# s3_dev.net
KiCad netlist of a schematic drawn in EasyEDA
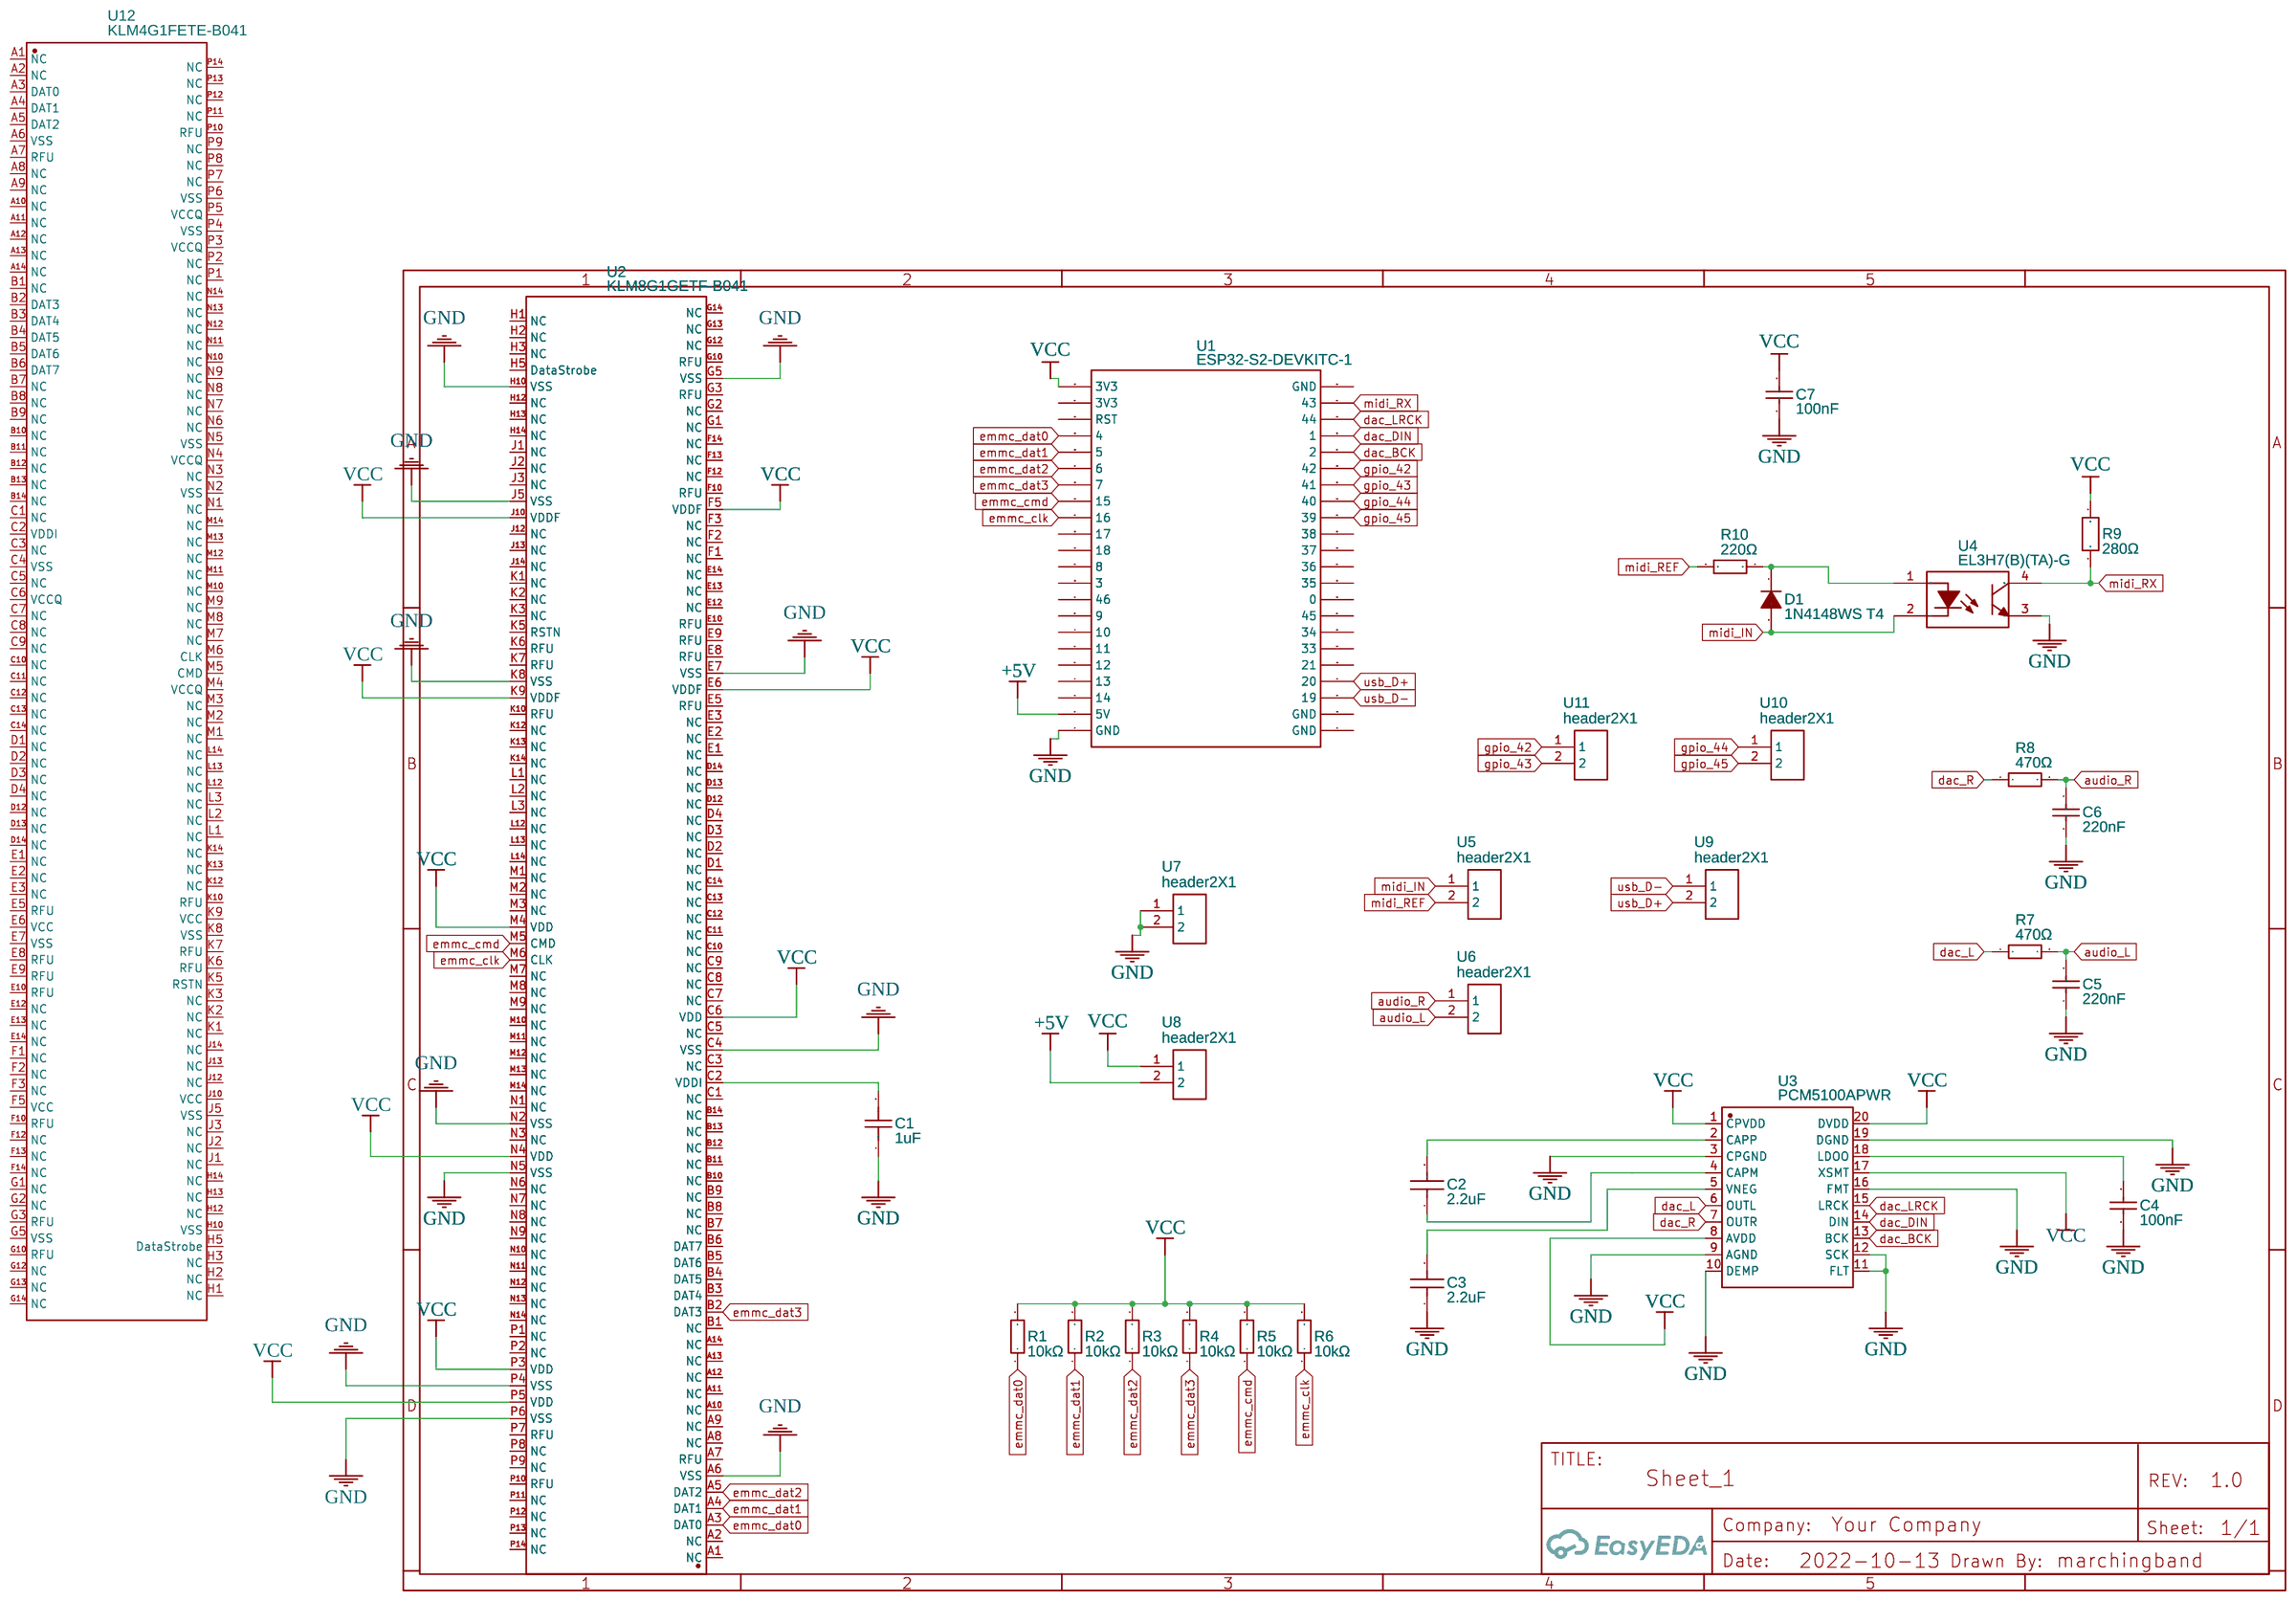
[diagram p0: schematic sheet]

(export (version "E")
  (design (tool "Eeschema 10.0.6"))
  (components
    (comp (ref "C1")
      (value "1uF")
      (fields
        (field (name "BOM_Manufacturer Part") "CL05A105KA5NQNC")
        (field (name "BOM_Supplier Part") "C52923")
      )
      (libsource (lib "") (part "CL05A105KA5NQNC"))
    )
    (comp (ref "C2")
      (value "2.2uF")
      (fields
        (field (name "BOM_Manufacturer Part") "CL05A225MQ5NSNC")
        (field (name "BOM_Supplier Part") "C12530")
      )
      (libsource (lib "") (part "CL05A225MQ5NSNC"))
    )
    (comp (ref "C3")
      (value "2.2uF")
      (fields
        (field (name "BOM_Manufacturer Part") "CL05A225MQ5NSNC")
        (field (name "BOM_Supplier Part") "C12530")
      )
      (libsource (lib "") (part "CL05A225MQ5NSNC"))
    )
    (comp (ref "C4")
      (value "100nF")
      (fields
        (field (name "BOM_Manufacturer Part") "CL05B104KO5NNNC")
        (field (name "BOM_Supplier Part") "C1525")
      )
      (libsource (lib "") (part "CL05B104KO5NNNC"))
    )
    (comp (ref "C5")
      (value "220nF")
      (fields
        (field (name "BOM_Manufacturer Part") "CL05B224KO5NNNC")
        (field (name "BOM_Supplier Part") "C16772")
      )
      (libsource (lib "") (part "CL05B224KO5NNNC"))
    )
    (comp (ref "C6")
      (value "220nF")
      (fields
        (field (name "BOM_Manufacturer Part") "CL05B224KO5NNNC")
        (field (name "BOM_Supplier Part") "C16772")
      )
      (libsource (lib "") (part "CL05B224KO5NNNC"))
    )
    (comp (ref "C7")
      (value "100nF")
      (fields
        (field (name "BOM_Manufacturer Part") "CL05B104KO5NNNC")
        (field (name "BOM_Supplier Part") "C1525")
      )
      (libsource (lib "") (part "CL05B104KO5NNNC"))
    )
    (comp (ref "D1")
      (value "1N4148WS T4")
      (fields (field (name "BOM_Supplier Part") "C2128"))
      (libsource (lib "") (part "1N4148WS T4"))
    )
    (comp (ref "R1")
      (value "10kΩ")
      (fields
        (field (name "BOM_Manufacturer Part") "0402WGF1002TCE")
        (field (name "BOM_Supplier Part") "C25744")
      )
      (libsource (lib "") (part "0402WGF1002TCE"))
    )
    (comp (ref "R2")
      (value "10kΩ")
      (fields
        (field (name "BOM_Manufacturer Part") "0402WGF1002TCE")
        (field (name "BOM_Supplier Part") "C25744")
      )
      (libsource (lib "") (part "0402WGF1002TCE"))
    )
    (comp (ref "R3")
      (value "10kΩ")
      (fields
        (field (name "BOM_Manufacturer Part") "0402WGF1002TCE")
        (field (name "BOM_Supplier Part") "C25744")
      )
      (libsource (lib "") (part "0402WGF1002TCE"))
    )
    (comp (ref "R4")
      (value "10kΩ")
      (fields
        (field (name "BOM_Manufacturer Part") "0402WGF1002TCE")
        (field (name "BOM_Supplier Part") "C25744")
      )
      (libsource (lib "") (part "0402WGF1002TCE"))
    )
    (comp (ref "R5")
      (value "10kΩ")
      (fields
        (field (name "BOM_Manufacturer Part") "0402WGF1002TCE")
        (field (name "BOM_Supplier Part") "C25744")
      )
      (libsource (lib "") (part "0402WGF1002TCE"))
    )
    (comp (ref "R6")
      (value "10kΩ")
      (fields
        (field (name "BOM_Manufacturer Part") "0402WGF1002TCE")
        (field (name "BOM_Supplier Part") "C25744")
      )
      (libsource (lib "") (part "0402WGF1002TCE"))
    )
    (comp (ref "R7")
      (value "470Ω")
      (fields
        (field (name "BOM_Manufacturer Part") "0402WGF4700TCE")
        (field (name "BOM_Supplier Part") "C25117")
      )
      (libsource (lib "") (part "0402WGF4700TCE"))
    )
    (comp (ref "R8")
      (value "470Ω")
      (fields
        (field (name "BOM_Manufacturer Part") "0402WGF4700TCE")
        (field (name "BOM_Supplier Part") "C25117")
      )
      (libsource (lib "") (part "0402WGF4700TCE"))
    )
    (comp (ref "R9")
      (value "280Ω")
      (fields
        (field (name "BOM_Manufacturer Part") "0402WGF2800TCE")
        (field (name "BOM_Supplier Part") "C423200")
      )
      (libsource (lib "") (part "0402WGF2800TCE"))
    )
    (comp (ref "R10")
      (value "220Ω")
      (fields
        (field (name "BOM_Manufacturer Part") "0402WGF2200TCE")
        (field (name "BOM_Supplier Part") "C25091")
      )
      (libsource (lib "") (part "0402WGF2200TCE"))
    )
    (comp (ref "U1")
      (value "ESP32-S2-DEVKITC-1")
      (fields (field (name "BOM_Supplier Part") "ESP32-S3-DevKitC-1"))
      (libsource (lib "") (part "ESP32-S2-DEVKITC-1"))
    )
    (comp (ref "U2")
      (value "KLM8G1GETF-B041")
      (fields (field (name "BOM_Supplier Part") "C499918"))
      (libsource (lib "") (part "KLM8G1GETF-B041"))
    )
    (comp (ref "U3")
      (value "PCM5100APWR")
      (fields (field (name "BOM_Supplier Part") "C131154"))
      (libsource (lib "") (part "PCM5100APWR"))
    )
    (comp (ref "U4")
      (value "EL3H7(B)(TA)-G")
      (fields (field (name "BOM_Supplier Part") "C32565"))
      (libsource (lib "") (part "EL3H7(B)(TA)-G"))
    )
    (comp (ref "U5") (value "header2X1") (libsource (lib "") (part "header2X1")))
    (comp (ref "U6") (value "header2X1") (libsource (lib "") (part "header2X1")))
    (comp (ref "U7") (value "header2X1") (libsource (lib "") (part "header2X1")))
    (comp (ref "U8") (value "header2X1") (libsource (lib "") (part "header2X1")))
    (comp (ref "U9") (value "header2X1") (libsource (lib "") (part "header2X1")))
    (comp (ref "U10") (value "header2X1") (libsource (lib "") (part "header2X1")))
    (comp (ref "U11") (value "header2X1") (libsource (lib "") (part "header2X1")))
    (comp (ref "U12")
      (value "KLM4G1FETE-B041")
      (fields (field (name "BOM_Supplier Part") "C500273"))
      (libsource (lib "") (part "KLM4G1FETE-B041"))
    )
  )
  (nets
    (net (code "1") (name "+5V") (class "Default")
      (node (ref "U1") (pin "2") (pinfunction "5V_2") (pintype "passive"))
      (node (ref "U8") (pin "2") (pinfunction "2_2") (pintype "unspecified"))
    )
    (net (code "2") (name "GND") (class "Default")
      (node (ref "C1") (pin "1") (pinfunction "1_1") (pintype "unspecified"))
      (node (ref "C3") (pin "1") (pinfunction "1_1") (pintype "unspecified"))
      (node (ref "C4") (pin "1") (pinfunction "1_1") (pintype "input"))
      (node (ref "C5") (pin "1") (pinfunction "1_1") (pintype "input"))
      (node (ref "C6") (pin "1") (pinfunction "1_1") (pintype "input"))
      (node (ref "C7") (pin "1") (pinfunction "1_1") (pintype "input"))
      (node (ref "U1") (pin "1") (pinfunction "GND_1") (pintype "unspecified"))
      (node (ref "U2") (pin "A6") (pinfunction "VSS_A6") (pintype "unspecified"))
      (node (ref "U2") (pin "C4") (pinfunction "VSS_C4") (pintype "unspecified"))
      (node (ref "U2") (pin "E7") (pinfunction "VSS_E7") (pintype "unspecified"))
      (node (ref "U2") (pin "G5") (pinfunction "VSS_G5") (pintype "unspecified"))
      (node (ref "U2") (pin "H10") (pinfunction "VSS_H10") (pintype "unspecified"))
      (node (ref "U2") (pin "J5") (pinfunction "VSS_J5") (pintype "unspecified"))
      (node (ref "U2") (pin "K8") (pinfunction "VSS_K8") (pintype "unspecified"))
      (node (ref "U2") (pin "N2") (pinfunction "VSS_N2") (pintype "unspecified"))
      (node (ref "U2") (pin "N5") (pinfunction "VSS_N5") (pintype "unspecified"))
      (node (ref "U2") (pin "P4") (pinfunction "VSS_P4") (pintype "unspecified"))
      (node (ref "U2") (pin "P6") (pinfunction "VSS_P6") (pintype "unspecified"))
      (node (ref "U3") (pin "10") (pinfunction "DEMP_10") (pintype "unspecified"))
      (node (ref "U3") (pin "11") (pinfunction "FLT_11") (pintype "unspecified"))
      (node (ref "U3") (pin "12") (pinfunction "SCK_12") (pintype "unspecified"))
      (node (ref "U3") (pin "16") (pinfunction "FMT_16") (pintype "unspecified"))
      (node (ref "U3") (pin "19") (pinfunction "DGND_19") (pintype "unspecified"))
      (node (ref "U3") (pin "3") (pinfunction "CPGND_3") (pintype "unspecified"))
      (node (ref "U3") (pin "9") (pinfunction "AGND_9") (pintype "unspecified"))
      (node (ref "U4") (pin "3") (pinfunction "EM_3") (pintype "unspecified"))
      (node (ref "U7") (pin "1") (pinfunction "1_1") (pintype "unspecified"))
      (node (ref "U7") (pin "2") (pinfunction "2_2") (pintype "unspecified"))
    )
    (net (code "3") (name "Net-(D1-K)") (class "Default")
      (node (ref "D1") (pin "1") (pinfunction "K_1") (pintype "unspecified"))
      (node (ref "R10") (pin "2") (pinfunction "2_2") (pintype "input"))
      (node (ref "U4") (pin "1") (pinfunction "AN_1") (pintype "unspecified"))
    )
    (net (code "4") (name "Net-(U2-VDDI)") (class "Default")
      (node (ref "C1") (pin "2") (pinfunction "2_2") (pintype "unspecified"))
      (node (ref "U2") (pin "C2") (pinfunction "VDDI_C2") (pintype "unspecified"))
    )
    (net (code "5") (name "Net-(U3-CAPM)") (class "Default")
      (node (ref "C2") (pin "1") (pinfunction "1_1") (pintype "unspecified"))
      (node (ref "U3") (pin "4") (pinfunction "CAPM_4") (pintype "unspecified"))
    )
    (net (code "6") (name "Net-(U3-CAPP)") (class "Default")
      (node (ref "C2") (pin "2") (pinfunction "2_2") (pintype "unspecified"))
      (node (ref "U3") (pin "2") (pinfunction "CAPP_2") (pintype "unspecified"))
    )
    (net (code "7") (name "Net-(U3-LDOO)") (class "Default")
      (node (ref "C4") (pin "2") (pinfunction "2_2") (pintype "input"))
      (node (ref "U3") (pin "18") (pinfunction "LDOO_18") (pintype "unspecified"))
    )
    (net (code "8") (name "Net-(U3-VNEG)") (class "Default")
      (node (ref "C3") (pin "2") (pinfunction "2_2") (pintype "unspecified"))
      (node (ref "U3") (pin "5") (pinfunction "VNEG_5") (pintype "unspecified"))
    )
    (net (code "9") (name "VCC") (class "Default")
      (node (ref "C7") (pin "2") (pinfunction "2_2") (pintype "input"))
      (node (ref "R1") (pin "2") (pinfunction "2_2") (pintype "input"))
      (node (ref "R2") (pin "2") (pinfunction "2_2") (pintype "input"))
      (node (ref "R3") (pin "2") (pinfunction "2_2") (pintype "input"))
      (node (ref "R4") (pin "2") (pinfunction "2_2") (pintype "input"))
      (node (ref "R5") (pin "2") (pinfunction "2_2") (pintype "input"))
      (node (ref "R6") (pin "2") (pinfunction "2_2") (pintype "input"))
      (node (ref "R9") (pin "2") (pinfunction "2_2") (pintype "unspecified"))
      (node (ref "U1") (pin "22") (pinfunction "3V3_22") (pintype "passive"))
      (node (ref "U2") (pin "C6") (pinfunction "VDD_C6") (pintype "unspecified"))
      (node (ref "U2") (pin "E6") (pinfunction "VDDF_E6") (pintype "unspecified"))
      (node (ref "U2") (pin "F5") (pinfunction "VDDF_F5") (pintype "unspecified"))
      (node (ref "U2") (pin "J10") (pinfunction "VDDF_J10") (pintype "unspecified"))
      (node (ref "U2") (pin "K9") (pinfunction "VDDF_K9") (pintype "unspecified"))
      (node (ref "U2") (pin "M4") (pinfunction "VDD_M4") (pintype "unspecified"))
      (node (ref "U2") (pin "N4") (pinfunction "VDD_N4") (pintype "unspecified"))
      (node (ref "U2") (pin "P3") (pinfunction "VDD_P3") (pintype "unspecified"))
      (node (ref "U2") (pin "P5") (pinfunction "VDD_P5") (pintype "unspecified"))
      (node (ref "U3") (pin "1") (pinfunction "CPVDD_1") (pintype "unspecified"))
      (node (ref "U3") (pin "17") (pinfunction "XSMT_17") (pintype "unspecified"))
      (node (ref "U3") (pin "20") (pinfunction "DVDD_20") (pintype "unspecified"))
      (node (ref "U3") (pin "8") (pinfunction "AVDD_8") (pintype "unspecified"))
      (node (ref "U8") (pin "1") (pinfunction "1_1") (pintype "unspecified"))
    )
    (net (code "10") (name "audio_L") (class "Default")
      (node (ref "C5") (pin "2") (pinfunction "2_2") (pintype "input"))
      (node (ref "R7") (pin "2") (pinfunction "2_2") (pintype "input"))
      (node (ref "U6") (pin "2") (pinfunction "2_2") (pintype "unspecified"))
    )
    (net (code "11") (name "audio_R") (class "Default")
      (node (ref "C6") (pin "2") (pinfunction "2_2") (pintype "input"))
      (node (ref "R8") (pin "2") (pinfunction "2_2") (pintype "input"))
      (node (ref "U6") (pin "1") (pinfunction "1_1") (pintype "unspecified"))
    )
    (net (code "12") (name "dac_BCK") (class "Default")
      (node (ref "U1") (pin "27") (pinfunction "2_27") (pintype "bidirectional"))
      (node (ref "U3") (pin "13") (pinfunction "BCK_13") (pintype "unspecified"))
    )
    (net (code "13") (name "dac_DIN") (class "Default")
      (node (ref "U1") (pin "26") (pinfunction "1_26") (pintype "bidirectional"))
      (node (ref "U3") (pin "14") (pinfunction "DIN_14") (pintype "unspecified"))
    )
    (net (code "14") (name "dac_L") (class "Default")
      (node (ref "R7") (pin "1") (pinfunction "1_1") (pintype "input"))
      (node (ref "U3") (pin "6") (pinfunction "OUTL_6") (pintype "unspecified"))
    )
    (net (code "15") (name "dac_LRCK") (class "Default")
      (node (ref "U1") (pin "25") (pinfunction "44_25") (pintype "bidirectional"))
      (node (ref "U3") (pin "15") (pinfunction "LRCK_15") (pintype "unspecified"))
    )
    (net (code "16") (name "dac_R") (class "Default")
      (node (ref "R8") (pin "1") (pinfunction "1_1") (pintype "input"))
      (node (ref "U3") (pin "7") (pinfunction "OUTR_7") (pintype "unspecified"))
    )
    (net (code "17") (name "emmc_clk") (class "Default")
      (node (ref "R6") (pin "1") (pinfunction "1_1") (pintype "input"))
      (node (ref "U1") (pin "14") (pinfunction "16_14") (pintype "bidirectional"))
      (node (ref "U2") (pin "M6") (pinfunction "CLK_M6") (pintype "unspecified"))
    )
    (net (code "18") (name "emmc_cmd") (class "Default")
      (node (ref "R5") (pin "1") (pinfunction "1_1") (pintype "input"))
      (node (ref "U1") (pin "15") (pinfunction "15_15") (pintype "bidirectional"))
      (node (ref "U2") (pin "M5") (pinfunction "CMD_M5") (pintype "unspecified"))
    )
    (net (code "19") (name "emmc_dat0") (class "Default")
      (node (ref "R1") (pin "1") (pinfunction "1_1") (pintype "input"))
      (node (ref "U1") (pin "19") (pinfunction "4_19") (pintype "bidirectional"))
      (node (ref "U2") (pin "A3") (pinfunction "DAT0_A3") (pintype "unspecified"))
    )
    (net (code "20") (name "emmc_dat1") (class "Default")
      (node (ref "R2") (pin "1") (pinfunction "1_1") (pintype "input"))
      (node (ref "U1") (pin "18") (pinfunction "5_18") (pintype "bidirectional"))
      (node (ref "U2") (pin "A4") (pinfunction "DAT1_A4") (pintype "unspecified"))
    )
    (net (code "21") (name "emmc_dat2") (class "Default")
      (node (ref "R3") (pin "1") (pinfunction "1_1") (pintype "input"))
      (node (ref "U1") (pin "17") (pinfunction "6_17") (pintype "bidirectional"))
      (node (ref "U2") (pin "A5") (pinfunction "DAT2_A5") (pintype "unspecified"))
    )
    (net (code "22") (name "emmc_dat3") (class "Default")
      (node (ref "R4") (pin "1") (pinfunction "1_1") (pintype "input"))
      (node (ref "U1") (pin "16") (pinfunction "7_16") (pintype "bidirectional"))
      (node (ref "U2") (pin "B2") (pinfunction "DAT3_B2") (pintype "unspecified"))
    )
    (net (code "23") (name "gpio_42") (class "Default")
      (node (ref "U1") (pin "28") (pinfunction "42_28") (pintype "bidirectional"))
      (node (ref "U11") (pin "1") (pinfunction "1_1") (pintype "unspecified"))
    )
    (net (code "24") (name "gpio_43") (class "Default")
      (node (ref "U1") (pin "29") (pinfunction "41_29") (pintype "bidirectional"))
      (node (ref "U11") (pin "2") (pinfunction "2_2") (pintype "unspecified"))
    )
    (net (code "25") (name "gpio_44") (class "Default")
      (node (ref "U1") (pin "30") (pinfunction "40_30") (pintype "bidirectional"))
      (node (ref "U10") (pin "1") (pinfunction "1_1") (pintype "unspecified"))
    )
    (net (code "26") (name "gpio_45") (class "Default")
      (node (ref "U1") (pin "31") (pinfunction "39_31") (pintype "bidirectional"))
      (node (ref "U10") (pin "2") (pinfunction "2_2") (pintype "unspecified"))
    )
    (net (code "27") (name "midi_IN") (class "Default")
      (node (ref "D1") (pin "2") (pinfunction "A_2") (pintype "unspecified"))
      (node (ref "U4") (pin "2") (pinfunction "CAT_2") (pintype "unspecified"))
      (node (ref "U5") (pin "1") (pinfunction "1_1") (pintype "unspecified"))
    )
    (net (code "28") (name "midi_REF") (class "Default")
      (node (ref "R10") (pin "1") (pinfunction "1_1") (pintype "input"))
      (node (ref "U5") (pin "2") (pinfunction "2_2") (pintype "unspecified"))
    )
    (net (code "29") (name "midi_RX") (class "Default")
      (node (ref "R9") (pin "1") (pinfunction "1_1") (pintype "unspecified"))
      (node (ref "U1") (pin "24") (pinfunction "43_24") (pintype "bidirectional"))
      (node (ref "U4") (pin "4") (pinfunction "COL_4") (pintype "unspecified"))
    )
    (net (code "30") (name "unconnected-(U1-0-Pad36)") (class "Default")
      (node (ref "U1") (pin "36") (pinfunction "0_36") (pintype "bidirectional"))
    )
    (net (code "31") (name "unconnected-(U1-3-Pad10)") (class "Default")
      (node (ref "U1") (pin "10") (pinfunction "3_10") (pintype "bidirectional"))
    )
    (net (code "32") (name "unconnected-(U1-3V3-Pad21)") (class "Default")
      (node (ref "U1") (pin "21") (pinfunction "3V3_21") (pintype "passive"))
    )
    (net (code "33") (name "unconnected-(U1-8-Pad11)") (class "Default")
      (node (ref "U1") (pin "11") (pinfunction "8_11") (pintype "bidirectional"))
    )
    (net (code "34") (name "unconnected-(U1-9-Pad8)") (class "Default")
      (node (ref "U1") (pin "8") (pinfunction "9_8") (pintype "bidirectional"))
    )
    (net (code "35") (name "unconnected-(U1-10-Pad7)") (class "Default")
      (node (ref "U1") (pin "7") (pinfunction "10_7") (pintype "bidirectional"))
    )
    (net (code "36") (name "unconnected-(U1-11-Pad6)") (class "Default")
      (node (ref "U1") (pin "6") (pinfunction "11_6") (pintype "bidirectional"))
    )
    (net (code "37") (name "unconnected-(U1-12-Pad5)") (class "Default")
      (node (ref "U1") (pin "5") (pinfunction "12_5") (pintype "bidirectional"))
    )
    (net (code "38") (name "unconnected-(U1-13-Pad4)") (class "Default")
      (node (ref "U1") (pin "4") (pinfunction "13_4") (pintype "bidirectional"))
    )
    (net (code "39") (name "unconnected-(U1-14-Pad3)") (class "Default")
      (node (ref "U1") (pin "3") (pinfunction "14_3") (pintype "bidirectional"))
    )
    (net (code "40") (name "unconnected-(U1-17-Pad13)") (class "Default")
      (node (ref "U1") (pin "13") (pinfunction "17_13") (pintype "bidirectional"))
    )
    (net (code "41") (name "unconnected-(U1-18-Pad12)") (class "Default")
      (node (ref "U1") (pin "12") (pinfunction "18_12") (pintype "bidirectional"))
    )
    (net (code "42") (name "unconnected-(U1-21-Pad40)") (class "Default")
      (node (ref "U1") (pin "40") (pinfunction "21_40") (pintype "bidirectional"))
    )
    (net (code "43") (name "unconnected-(U1-33-Pad39)") (class "Default")
      (node (ref "U1") (pin "39") (pinfunction "33_39") (pintype "bidirectional"))
    )
    (net (code "44") (name "unconnected-(U1-34-Pad38)") (class "Default")
      (node (ref "U1") (pin "38") (pinfunction "34_38") (pintype "bidirectional"))
    )
    (net (code "45") (name "unconnected-(U1-36-Pad34)") (class "Default")
      (node (ref "U1") (pin "34") (pinfunction "36_34") (pintype "bidirectional"))
    )
    (net (code "46") (name "unconnected-(U1-37-Pad33)") (class "Default")
      (node (ref "U1") (pin "33") (pinfunction "37_33") (pintype "bidirectional"))
    )
    (net (code "47") (name "unconnected-(U1-38-Pad32)") (class "Default")
      (node (ref "U1") (pin "32") (pinfunction "38_32") (pintype "bidirectional"))
    )
    (net (code "48") (name "unconnected-(U1-45-Pad37)") (class "Default")
      (node (ref "U1") (pin "37") (pinfunction "45_37") (pintype "bidirectional"))
    )
    (net (code "49") (name "unconnected-(U1-46-Pad9)") (class "Default")
      (node (ref "U1") (pin "9") (pinfunction "46_9") (pintype "bidirectional"))
    )
    (net (code "50") (name "unconnected-(U1-GND-Pad23)") (class "Default")
      (node (ref "U1") (pin "23") (pinfunction "GND_23") (pintype "unspecified"))
    )
    (net (code "51") (name "unconnected-(U1-GND-Pad43)") (class "Default")
      (node (ref "U1") (pin "43") (pinfunction "GND_43") (pintype "bidirectional"))
    )
    (net (code "52") (name "unconnected-(U1-GND-Pad44)") (class "Default")
      (node (ref "U1") (pin "44") (pinfunction "GND_44") (pintype "unspecified"))
    )
    (net (code "53") (name "unconnected-(U1-Pad35)") (class "Default")
      (node (ref "U1") (pin "35") (pinfunction "35_35") (pintype "bidirectional"))
    )
    (net (code "54") (name "unconnected-(U1-RST-Pad20)") (class "Default")
      (node (ref "U1") (pin "20") (pinfunction "RST_20") (pintype "unspecified"))
    )
    (net (code "55") (name "unconnected-(U2-DAT4-PadB3)") (class "Default")
      (node (ref "U2") (pin "B3") (pinfunction "DAT4_B3") (pintype "unspecified"))
    )
    (net (code "56") (name "unconnected-(U2-DAT5-PadB4)") (class "Default")
      (node (ref "U2") (pin "B4") (pinfunction "DAT5_B4") (pintype "unspecified"))
    )
    (net (code "57") (name "unconnected-(U2-DAT6-PadB5)") (class "Default")
      (node (ref "U2") (pin "B5") (pinfunction "DAT6_B5") (pintype "unspecified"))
    )
    (net (code "58") (name "unconnected-(U2-DAT7-PadB6)") (class "Default")
      (node (ref "U2") (pin "B6") (pinfunction "DAT7_B6") (pintype "unspecified"))
    )
    (net (code "59") (name "unconnected-(U2-DataStrobe-PadH5)") (class "Default")
      (node (ref "U2") (pin "H5") (pinfunction "DataStrobe_H5") (pintype "unspecified"))
    )
    (net (code "60") (name "unconnected-(U2-NC-PadA1)") (class "Default")
      (node (ref "U2") (pin "A1") (pinfunction "NC_A1") (pintype "unspecified"))
    )
    (net (code "61") (name "unconnected-(U2-NC-PadA2)") (class "Default")
      (node (ref "U2") (pin "A2") (pinfunction "NC_A2") (pintype "unspecified"))
    )
    (net (code "62") (name "unconnected-(U2-NC-PadA8)") (class "Default")
      (node (ref "U2") (pin "A8") (pinfunction "NC_A8") (pintype "unspecified"))
    )
    (net (code "63") (name "unconnected-(U2-NC-PadA9)") (class "Default")
      (node (ref "U2") (pin "A9") (pinfunction "NC_A9") (pintype "unspecified"))
    )
    (net (code "64") (name "unconnected-(U2-NC-PadA10)") (class "Default")
      (node (ref "U2") (pin "A10") (pinfunction "NC_A10") (pintype "unspecified"))
    )
    (net (code "65") (name "unconnected-(U2-NC-PadA11)") (class "Default")
      (node (ref "U2") (pin "A11") (pinfunction "NC_A11") (pintype "unspecified"))
    )
    (net (code "66") (name "unconnected-(U2-NC-PadA12)") (class "Default")
      (node (ref "U2") (pin "A12") (pinfunction "NC_A12") (pintype "unspecified"))
    )
    (net (code "67") (name "unconnected-(U2-NC-PadA13)") (class "Default")
      (node (ref "U2") (pin "A13") (pinfunction "NC_A13") (pintype "unspecified"))
    )
    (net (code "68") (name "unconnected-(U2-NC-PadA14)") (class "Default")
      (node (ref "U2") (pin "A14") (pinfunction "NC_A14") (pintype "unspecified"))
    )
    (net (code "69") (name "unconnected-(U2-NC-PadB1)") (class "Default")
      (node (ref "U2") (pin "B1") (pinfunction "NC_B1") (pintype "unspecified"))
    )
    (net (code "70") (name "unconnected-(U2-NC-PadB7)") (class "Default")
      (node (ref "U2") (pin "B7") (pinfunction "NC_B7") (pintype "unspecified"))
    )
    (net (code "71") (name "unconnected-(U2-NC-PadB8)") (class "Default")
      (node (ref "U2") (pin "B8") (pinfunction "NC_B8") (pintype "unspecified"))
    )
    (net (code "72") (name "unconnected-(U2-NC-PadB9)") (class "Default")
      (node (ref "U2") (pin "B9") (pinfunction "NC_B9") (pintype "unspecified"))
    )
    (net (code "73") (name "unconnected-(U2-NC-PadB10)") (class "Default")
      (node (ref "U2") (pin "B10") (pinfunction "NC_B10") (pintype "unspecified"))
    )
    (net (code "74") (name "unconnected-(U2-NC-PadB11)") (class "Default")
      (node (ref "U2") (pin "B11") (pinfunction "NC_B11") (pintype "unspecified"))
    )
    (net (code "75") (name "unconnected-(U2-NC-PadB12)") (class "Default")
      (node (ref "U2") (pin "B12") (pinfunction "NC_B12") (pintype "unspecified"))
    )
    (net (code "76") (name "unconnected-(U2-NC-PadB13)") (class "Default")
      (node (ref "U2") (pin "B13") (pinfunction "NC_B13") (pintype "unspecified"))
    )
    (net (code "77") (name "unconnected-(U2-NC-PadB14)") (class "Default")
      (node (ref "U2") (pin "B14") (pinfunction "NC_B14") (pintype "unspecified"))
    )
    (net (code "78") (name "unconnected-(U2-NC-PadC1)") (class "Default")
      (node (ref "U2") (pin "C1") (pinfunction "NC_C1") (pintype "unspecified"))
    )
    (net (code "79") (name "unconnected-(U2-NC-PadC3)") (class "Default")
      (node (ref "U2") (pin "C3") (pinfunction "NC_C3") (pintype "unspecified"))
    )
    (net (code "80") (name "unconnected-(U2-NC-PadC5)") (class "Default")
      (node (ref "U2") (pin "C5") (pinfunction "NC_C5") (pintype "unspecified"))
    )
    (net (code "81") (name "unconnected-(U2-NC-PadC7)") (class "Default")
      (node (ref "U2") (pin "C7") (pinfunction "NC_C7") (pintype "unspecified"))
    )
    (net (code "82") (name "unconnected-(U2-NC-PadC8)") (class "Default")
      (node (ref "U2") (pin "C8") (pinfunction "NC_C8") (pintype "unspecified"))
    )
    (net (code "83") (name "unconnected-(U2-NC-PadC9)") (class "Default")
      (node (ref "U2") (pin "C9") (pinfunction "NC_C9") (pintype "unspecified"))
    )
    (net (code "84") (name "unconnected-(U2-NC-PadC10)") (class "Default")
      (node (ref "U2") (pin "C10") (pinfunction "NC_C10") (pintype "unspecified"))
    )
    (net (code "85") (name "unconnected-(U2-NC-PadC11)") (class "Default")
      (node (ref "U2") (pin "C11") (pinfunction "NC_C11") (pintype "unspecified"))
    )
    (net (code "86") (name "unconnected-(U2-NC-PadC12)") (class "Default")
      (node (ref "U2") (pin "C12") (pinfunction "NC_C12") (pintype "unspecified"))
    )
    (net (code "87") (name "unconnected-(U2-NC-PadC13)") (class "Default")
      (node (ref "U2") (pin "C13") (pinfunction "NC_C13") (pintype "unspecified"))
    )
    (net (code "88") (name "unconnected-(U2-NC-PadC14)") (class "Default")
      (node (ref "U2") (pin "C14") (pinfunction "NC_C14") (pintype "unspecified"))
    )
    (net (code "89") (name "unconnected-(U2-NC-PadD1)") (class "Default")
      (node (ref "U2") (pin "D1") (pinfunction "NC_D1") (pintype "unspecified"))
    )
    (net (code "90") (name "unconnected-(U2-NC-PadD2)") (class "Default")
      (node (ref "U2") (pin "D2") (pinfunction "NC_D2") (pintype "unspecified"))
    )
    (net (code "91") (name "unconnected-(U2-NC-PadD3)") (class "Default")
      (node (ref "U2") (pin "D3") (pinfunction "NC_D3") (pintype "unspecified"))
    )
    (net (code "92") (name "unconnected-(U2-NC-PadD4)") (class "Default")
      (node (ref "U2") (pin "D4") (pinfunction "NC_D4") (pintype "unspecified"))
    )
    (net (code "93") (name "unconnected-(U2-NC-PadD12)") (class "Default")
      (node (ref "U2") (pin "D12") (pinfunction "NC_D12") (pintype "unspecified"))
    )
    (net (code "94") (name "unconnected-(U2-NC-PadD13)") (class "Default")
      (node (ref "U2") (pin "D13") (pinfunction "NC_D13") (pintype "unspecified"))
    )
    (net (code "95") (name "unconnected-(U2-NC-PadD14)") (class "Default")
      (node (ref "U2") (pin "D14") (pinfunction "NC_D14") (pintype "unspecified"))
    )
    (net (code "96") (name "unconnected-(U2-NC-PadE1)") (class "Default")
      (node (ref "U2") (pin "E1") (pinfunction "NC_E1") (pintype "unspecified"))
    )
    (net (code "97") (name "unconnected-(U2-NC-PadE2)") (class "Default")
      (node (ref "U2") (pin "E2") (pinfunction "NC_E2") (pintype "unspecified"))
    )
    (net (code "98") (name "unconnected-(U2-NC-PadE3)") (class "Default")
      (node (ref "U2") (pin "E3") (pinfunction "NC_E3") (pintype "unspecified"))
    )
    (net (code "99") (name "unconnected-(U2-NC-PadE12)") (class "Default")
      (node (ref "U2") (pin "E12") (pinfunction "NC_E12") (pintype "unspecified"))
    )
    (net (code "100") (name "unconnected-(U2-NC-PadE13)") (class "Default")
      (node (ref "U2") (pin "E13") (pinfunction "NC_E13") (pintype "unspecified"))
    )
    (net (code "101") (name "unconnected-(U2-NC-PadE14)") (class "Default")
      (node (ref "U2") (pin "E14") (pinfunction "NC_E14") (pintype "unspecified"))
    )
    (net (code "102") (name "unconnected-(U2-NC-PadF1)") (class "Default")
      (node (ref "U2") (pin "F1") (pinfunction "NC_F1") (pintype "unspecified"))
    )
    (net (code "103") (name "unconnected-(U2-NC-PadF2)") (class "Default")
      (node (ref "U2") (pin "F2") (pinfunction "NC_F2") (pintype "unspecified"))
    )
    (net (code "104") (name "unconnected-(U2-NC-PadF3)") (class "Default")
      (node (ref "U2") (pin "F3") (pinfunction "NC_F3") (pintype "unspecified"))
    )
    (net (code "105") (name "unconnected-(U2-NC-PadF12)") (class "Default")
      (node (ref "U2") (pin "F12") (pinfunction "NC_F12") (pintype "unspecified"))
    )
    (net (code "106") (name "unconnected-(U2-NC-PadF13)") (class "Default")
      (node (ref "U2") (pin "F13") (pinfunction "NC_F13") (pintype "unspecified"))
    )
    (net (code "107") (name "unconnected-(U2-NC-PadF14)") (class "Default")
      (node (ref "U2") (pin "F14") (pinfunction "NC_F14") (pintype "unspecified"))
    )
    (net (code "108") (name "unconnected-(U2-NC-PadG1)") (class "Default")
      (node (ref "U2") (pin "G1") (pinfunction "NC_G1") (pintype "unspecified"))
    )
    (net (code "109") (name "unconnected-(U2-NC-PadG2)") (class "Default")
      (node (ref "U2") (pin "G2") (pinfunction "NC_G2") (pintype "unspecified"))
    )
    (net (code "110") (name "unconnected-(U2-NC-PadG12)") (class "Default")
      (node (ref "U2") (pin "G12") (pinfunction "NC_G12") (pintype "unspecified"))
    )
    (net (code "111") (name "unconnected-(U2-NC-PadG13)") (class "Default")
      (node (ref "U2") (pin "G13") (pinfunction "NC_G13") (pintype "unspecified"))
    )
    (net (code "112") (name "unconnected-(U2-NC-PadG14)") (class "Default")
      (node (ref "U2") (pin "G14") (pinfunction "NC_G14") (pintype "unspecified"))
    )
    (net (code "113") (name "unconnected-(U2-NC-PadH1)") (class "Default")
      (node (ref "U2") (pin "H1") (pinfunction "NC_H1") (pintype "unspecified"))
    )
    (net (code "114") (name "unconnected-(U2-NC-PadH2)") (class "Default")
      (node (ref "U2") (pin "H2") (pinfunction "NC_H2") (pintype "unspecified"))
    )
    (net (code "115") (name "unconnected-(U2-NC-PadH3)") (class "Default")
      (node (ref "U2") (pin "H3") (pinfunction "NC_H3") (pintype "unspecified"))
    )
    (net (code "116") (name "unconnected-(U2-NC-PadH12)") (class "Default")
      (node (ref "U2") (pin "H12") (pinfunction "NC_H12") (pintype "unspecified"))
    )
    (net (code "117") (name "unconnected-(U2-NC-PadH13)") (class "Default")
      (node (ref "U2") (pin "H13") (pinfunction "NC_H13") (pintype "unspecified"))
    )
    (net (code "118") (name "unconnected-(U2-NC-PadH14)") (class "Default")
      (node (ref "U2") (pin "H14") (pinfunction "NC_H14") (pintype "unspecified"))
    )
    (net (code "119") (name "unconnected-(U2-NC-PadJ1)") (class "Default")
      (node (ref "U2") (pin "J1") (pinfunction "NC_J1") (pintype "unspecified"))
    )
    (net (code "120") (name "unconnected-(U2-NC-PadJ2)") (class "Default")
      (node (ref "U2") (pin "J2") (pinfunction "NC_J2") (pintype "unspecified"))
    )
    (net (code "121") (name "unconnected-(U2-NC-PadJ3)") (class "Default")
      (node (ref "U2") (pin "J3") (pinfunction "NC_J3") (pintype "unspecified"))
    )
    (net (code "122") (name "unconnected-(U2-NC-PadJ12)") (class "Default")
      (node (ref "U2") (pin "J12") (pinfunction "NC_J12") (pintype "unspecified"))
    )
    (net (code "123") (name "unconnected-(U2-NC-PadJ13)") (class "Default")
      (node (ref "U2") (pin "J13") (pinfunction "NC_J13") (pintype "unspecified"))
    )
    (net (code "124") (name "unconnected-(U2-NC-PadJ14)") (class "Default")
      (node (ref "U2") (pin "J14") (pinfunction "NC_J14") (pintype "unspecified"))
    )
    (net (code "125") (name "unconnected-(U2-NC-PadK1)") (class "Default")
      (node (ref "U2") (pin "K1") (pinfunction "NC_K1") (pintype "unspecified"))
    )
    (net (code "126") (name "unconnected-(U2-NC-PadK2)") (class "Default")
      (node (ref "U2") (pin "K2") (pinfunction "NC_K2") (pintype "unspecified"))
    )
    (net (code "127") (name "unconnected-(U2-NC-PadK3)") (class "Default")
      (node (ref "U2") (pin "K3") (pinfunction "NC_K3") (pintype "unspecified"))
    )
    (net (code "128") (name "unconnected-(U2-NC-PadK12)") (class "Default")
      (node (ref "U2") (pin "K12") (pinfunction "NC_K12") (pintype "unspecified"))
    )
    (net (code "129") (name "unconnected-(U2-NC-PadK13)") (class "Default")
      (node (ref "U2") (pin "K13") (pinfunction "NC_K13") (pintype "unspecified"))
    )
    (net (code "130") (name "unconnected-(U2-NC-PadK14)") (class "Default")
      (node (ref "U2") (pin "K14") (pinfunction "NC_K14") (pintype "unspecified"))
    )
    (net (code "131") (name "unconnected-(U2-NC-PadL1)") (class "Default")
      (node (ref "U2") (pin "L1") (pinfunction "NC_L1") (pintype "unspecified"))
    )
    (net (code "132") (name "unconnected-(U2-NC-PadL2)") (class "Default")
      (node (ref "U2") (pin "L2") (pinfunction "NC_L2") (pintype "unspecified"))
    )
    (net (code "133") (name "unconnected-(U2-NC-PadL3)") (class "Default")
      (node (ref "U2") (pin "L3") (pinfunction "NC_L3") (pintype "unspecified"))
    )
    (net (code "134") (name "unconnected-(U2-NC-PadL12)") (class "Default")
      (node (ref "U2") (pin "L12") (pinfunction "NC_L12") (pintype "unspecified"))
    )
    (net (code "135") (name "unconnected-(U2-NC-PadL13)") (class "Default")
      (node (ref "U2") (pin "L13") (pinfunction "NC_L13") (pintype "unspecified"))
    )
    (net (code "136") (name "unconnected-(U2-NC-PadL14)") (class "Default")
      (node (ref "U2") (pin "L14") (pinfunction "NC_L14") (pintype "unspecified"))
    )
    (net (code "137") (name "unconnected-(U2-NC-PadM1)") (class "Default")
      (node (ref "U2") (pin "M1") (pinfunction "NC_M1") (pintype "unspecified"))
    )
    (net (code "138") (name "unconnected-(U2-NC-PadM2)") (class "Default")
      (node (ref "U2") (pin "M2") (pinfunction "NC_M2") (pintype "unspecified"))
    )
    (net (code "139") (name "unconnected-(U2-NC-PadM3)") (class "Default")
      (node (ref "U2") (pin "M3") (pinfunction "NC_M3") (pintype "unspecified"))
    )
    (net (code "140") (name "unconnected-(U2-NC-PadM7)") (class "Default")
      (node (ref "U2") (pin "M7") (pinfunction "NC_M7") (pintype "unspecified"))
    )
    (net (code "141") (name "unconnected-(U2-NC-PadM8)") (class "Default")
      (node (ref "U2") (pin "M8") (pinfunction "NC_M8") (pintype "unspecified"))
    )
    (net (code "142") (name "unconnected-(U2-NC-PadM9)") (class "Default")
      (node (ref "U2") (pin "M9") (pinfunction "NC_M9") (pintype "unspecified"))
    )
    (net (code "143") (name "unconnected-(U2-NC-PadM10)") (class "Default")
      (node (ref "U2") (pin "M10") (pinfunction "NC_M10") (pintype "unspecified"))
    )
    (net (code "144") (name "unconnected-(U2-NC-PadM11)") (class "Default")
      (node (ref "U2") (pin "M11") (pinfunction "NC_M11") (pintype "unspecified"))
    )
    (net (code "145") (name "unconnected-(U2-NC-PadM12)") (class "Default")
      (node (ref "U2") (pin "M12") (pinfunction "NC_M12") (pintype "unspecified"))
    )
    (net (code "146") (name "unconnected-(U2-NC-PadM13)") (class "Default")
      (node (ref "U2") (pin "M13") (pinfunction "NC_M13") (pintype "unspecified"))
    )
    (net (code "147") (name "unconnected-(U2-NC-PadM14)") (class "Default")
      (node (ref "U2") (pin "M14") (pinfunction "NC_M14") (pintype "unspecified"))
    )
    (net (code "148") (name "unconnected-(U2-NC-PadN1)") (class "Default")
      (node (ref "U2") (pin "N1") (pinfunction "NC_N1") (pintype "unspecified"))
    )
    (net (code "149") (name "unconnected-(U2-NC-PadN3)") (class "Default")
      (node (ref "U2") (pin "N3") (pinfunction "NC_N3") (pintype "unspecified"))
    )
    (net (code "150") (name "unconnected-(U2-NC-PadN6)") (class "Default")
      (node (ref "U2") (pin "N6") (pinfunction "NC_N6") (pintype "unspecified"))
    )
    (net (code "151") (name "unconnected-(U2-NC-PadN7)") (class "Default")
      (node (ref "U2") (pin "N7") (pinfunction "NC_N7") (pintype "unspecified"))
    )
    (net (code "152") (name "unconnected-(U2-NC-PadN8)") (class "Default")
      (node (ref "U2") (pin "N8") (pinfunction "NC_N8") (pintype "unspecified"))
    )
    (net (code "153") (name "unconnected-(U2-NC-PadN9)") (class "Default")
      (node (ref "U2") (pin "N9") (pinfunction "NC_N9") (pintype "unspecified"))
    )
    (net (code "154") (name "unconnected-(U2-NC-PadN10)") (class "Default")
      (node (ref "U2") (pin "N10") (pinfunction "NC_N10") (pintype "unspecified"))
    )
    (net (code "155") (name "unconnected-(U2-NC-PadN11)") (class "Default")
      (node (ref "U2") (pin "N11") (pinfunction "NC_N11") (pintype "unspecified"))
    )
    (net (code "156") (name "unconnected-(U2-NC-PadN12)") (class "Default")
      (node (ref "U2") (pin "N12") (pinfunction "NC_N12") (pintype "unspecified"))
    )
    (net (code "157") (name "unconnected-(U2-NC-PadN13)") (class "Default")
      (node (ref "U2") (pin "N13") (pinfunction "NC_N13") (pintype "unspecified"))
    )
    (net (code "158") (name "unconnected-(U2-NC-PadN14)") (class "Default")
      (node (ref "U2") (pin "N14") (pinfunction "NC_N14") (pintype "unspecified"))
    )
    (net (code "159") (name "unconnected-(U2-NC-PadP1)") (class "Default")
      (node (ref "U2") (pin "P1") (pinfunction "NC_P1") (pintype "unspecified"))
    )
    (net (code "160") (name "unconnected-(U2-NC-PadP2)") (class "Default")
      (node (ref "U2") (pin "P2") (pinfunction "NC_P2") (pintype "unspecified"))
    )
    (net (code "161") (name "unconnected-(U2-NC-PadP8)") (class "Default")
      (node (ref "U2") (pin "P8") (pinfunction "NC_P8") (pintype "unspecified"))
    )
    (net (code "162") (name "unconnected-(U2-NC-PadP9)") (class "Default")
      (node (ref "U2") (pin "P9") (pinfunction "NC_P9") (pintype "unspecified"))
    )
    (net (code "163") (name "unconnected-(U2-NC-PadP11)") (class "Default")
      (node (ref "U2") (pin "P11") (pinfunction "NC_P11") (pintype "unspecified"))
    )
    (net (code "164") (name "unconnected-(U2-NC-PadP12)") (class "Default")
      (node (ref "U2") (pin "P12") (pinfunction "NC_P12") (pintype "unspecified"))
    )
    (net (code "165") (name "unconnected-(U2-NC-PadP13)") (class "Default")
      (node (ref "U2") (pin "P13") (pinfunction "NC_P13") (pintype "unspecified"))
    )
    (net (code "166") (name "unconnected-(U2-NC-PadP14)") (class "Default")
      (node (ref "U2") (pin "P14") (pinfunction "NC_P14") (pintype "unspecified"))
    )
    (net (code "167") (name "unconnected-(U2-RFU-PadA7)") (class "Default")
      (node (ref "U2") (pin "A7") (pinfunction "RFU_A7") (pintype "unspecified"))
    )
    (net (code "168") (name "unconnected-(U2-RFU-PadE5)") (class "Default")
      (node (ref "U2") (pin "E5") (pinfunction "RFU_E5") (pintype "unspecified"))
    )
    (net (code "169") (name "unconnected-(U2-RFU-PadE8)") (class "Default")
      (node (ref "U2") (pin "E8") (pinfunction "RFU_E8") (pintype "unspecified"))
    )
    (net (code "170") (name "unconnected-(U2-RFU-PadE9)") (class "Default")
      (node (ref "U2") (pin "E9") (pinfunction "RFU_E9") (pintype "unspecified"))
    )
    (net (code "171") (name "unconnected-(U2-RFU-PadE10)") (class "Default")
      (node (ref "U2") (pin "E10") (pinfunction "RFU_E10") (pintype "unspecified"))
    )
    (net (code "172") (name "unconnected-(U2-RFU-PadF10)") (class "Default")
      (node (ref "U2") (pin "F10") (pinfunction "RFU_F10") (pintype "unspecified"))
    )
    (net (code "173") (name "unconnected-(U2-RFU-PadG3)") (class "Default")
      (node (ref "U2") (pin "G3") (pinfunction "RFU_G3") (pintype "unspecified"))
    )
    (net (code "174") (name "unconnected-(U2-RFU-PadG10)") (class "Default")
      (node (ref "U2") (pin "G10") (pinfunction "RFU_G10") (pintype "unspecified"))
    )
    (net (code "175") (name "unconnected-(U2-RFU-PadK6)") (class "Default")
      (node (ref "U2") (pin "K6") (pinfunction "RFU_K6") (pintype "unspecified"))
    )
    (net (code "176") (name "unconnected-(U2-RFU-PadK7)") (class "Default")
      (node (ref "U2") (pin "K7") (pinfunction "RFU_K7") (pintype "unspecified"))
    )
    (net (code "177") (name "unconnected-(U2-RFU-PadK10)") (class "Default")
      (node (ref "U2") (pin "K10") (pinfunction "RFU_K10") (pintype "unspecified"))
    )
    (net (code "178") (name "unconnected-(U2-RFU-PadP7)") (class "Default")
      (node (ref "U2") (pin "P7") (pinfunction "RFU_P7") (pintype "unspecified"))
    )
    (net (code "179") (name "unconnected-(U2-RFU-PadP10)") (class "Default")
      (node (ref "U2") (pin "P10") (pinfunction "RFU_P10") (pintype "unspecified"))
    )
    (net (code "180") (name "unconnected-(U2-RSTN-PadK5)") (class "Default")
      (node (ref "U2") (pin "K5") (pinfunction "RSTN_K5") (pintype "unspecified"))
    )
    (net (code "181") (name "unconnected-(U12-CLK-PadM6)") (class "Default")
      (node (ref "U12") (pin "M6") (pinfunction "CLK_M6") (pintype "unspecified"))
    )
    (net (code "182") (name "unconnected-(U12-CMD-PadM5)") (class "Default")
      (node (ref "U12") (pin "M5") (pinfunction "CMD_M5") (pintype "unspecified"))
    )
    (net (code "183") (name "unconnected-(U12-DAT0-PadA3)") (class "Default")
      (node (ref "U12") (pin "A3") (pinfunction "DAT0_A3") (pintype "unspecified"))
    )
    (net (code "184") (name "unconnected-(U12-DAT1-PadA4)") (class "Default")
      (node (ref "U12") (pin "A4") (pinfunction "DAT1_A4") (pintype "unspecified"))
    )
    (net (code "185") (name "unconnected-(U12-DAT2-PadA5)") (class "Default")
      (node (ref "U12") (pin "A5") (pinfunction "DAT2_A5") (pintype "unspecified"))
    )
    (net (code "186") (name "unconnected-(U12-DAT3-PadB2)") (class "Default")
      (node (ref "U12") (pin "B2") (pinfunction "DAT3_B2") (pintype "unspecified"))
    )
    (net (code "187") (name "unconnected-(U12-DAT4-PadB3)") (class "Default")
      (node (ref "U12") (pin "B3") (pinfunction "DAT4_B3") (pintype "unspecified"))
    )
    (net (code "188") (name "unconnected-(U12-DAT5-PadB4)") (class "Default")
      (node (ref "U12") (pin "B4") (pinfunction "DAT5_B4") (pintype "unspecified"))
    )
    (net (code "189") (name "unconnected-(U12-DAT6-PadB5)") (class "Default")
      (node (ref "U12") (pin "B5") (pinfunction "DAT6_B5") (pintype "unspecified"))
    )
    (net (code "190") (name "unconnected-(U12-DAT7-PadB6)") (class "Default")
      (node (ref "U12") (pin "B6") (pinfunction "DAT7_B6") (pintype "unspecified"))
    )
    (net (code "191") (name "unconnected-(U12-DataStrobe-PadH5)") (class "Default")
      (node (ref "U12") (pin "H5") (pinfunction "DataStrobe_H5") (pintype "unspecified"))
    )
    (net (code "192") (name "unconnected-(U12-NC-PadA1)") (class "Default")
      (node (ref "U12") (pin "A1") (pinfunction "NC_A1") (pintype "unspecified"))
    )
    (net (code "193") (name "unconnected-(U12-NC-PadA2)") (class "Default")
      (node (ref "U12") (pin "A2") (pinfunction "NC_A2") (pintype "unspecified"))
    )
    (net (code "194") (name "unconnected-(U12-NC-PadA8)") (class "Default")
      (node (ref "U12") (pin "A8") (pinfunction "NC_A8") (pintype "unspecified"))
    )
    (net (code "195") (name "unconnected-(U12-NC-PadA9)") (class "Default")
      (node (ref "U12") (pin "A9") (pinfunction "NC_A9") (pintype "unspecified"))
    )
    (net (code "196") (name "unconnected-(U12-NC-PadA10)") (class "Default")
      (node (ref "U12") (pin "A10") (pinfunction "NC_A10") (pintype "unspecified"))
    )
    (net (code "197") (name "unconnected-(U12-NC-PadA11)") (class "Default")
      (node (ref "U12") (pin "A11") (pinfunction "NC_A11") (pintype "unspecified"))
    )
    (net (code "198") (name "unconnected-(U12-NC-PadA12)") (class "Default")
      (node (ref "U12") (pin "A12") (pinfunction "NC_A12") (pintype "unspecified"))
    )
    (net (code "199") (name "unconnected-(U12-NC-PadA13)") (class "Default")
      (node (ref "U12") (pin "A13") (pinfunction "NC_A13") (pintype "unspecified"))
    )
    (net (code "200") (name "unconnected-(U12-NC-PadA14)") (class "Default")
      (node (ref "U12") (pin "A14") (pinfunction "NC_A14") (pintype "unspecified"))
    )
    (net (code "201") (name "unconnected-(U12-NC-PadB1)") (class "Default")
      (node (ref "U12") (pin "B1") (pinfunction "NC_B1") (pintype "unspecified"))
    )
    (net (code "202") (name "unconnected-(U12-NC-PadB7)") (class "Default")
      (node (ref "U12") (pin "B7") (pinfunction "NC_B7") (pintype "unspecified"))
    )
    (net (code "203") (name "unconnected-(U12-NC-PadB8)") (class "Default")
      (node (ref "U12") (pin "B8") (pinfunction "NC_B8") (pintype "unspecified"))
    )
    (net (code "204") (name "unconnected-(U12-NC-PadB9)") (class "Default")
      (node (ref "U12") (pin "B9") (pinfunction "NC_B9") (pintype "unspecified"))
    )
    (net (code "205") (name "unconnected-(U12-NC-PadB10)") (class "Default")
      (node (ref "U12") (pin "B10") (pinfunction "NC_B10") (pintype "unspecified"))
    )
    (net (code "206") (name "unconnected-(U12-NC-PadB11)") (class "Default")
      (node (ref "U12") (pin "B11") (pinfunction "NC_B11") (pintype "unspecified"))
    )
    (net (code "207") (name "unconnected-(U12-NC-PadB12)") (class "Default")
      (node (ref "U12") (pin "B12") (pinfunction "NC_B12") (pintype "unspecified"))
    )
    (net (code "208") (name "unconnected-(U12-NC-PadB13)") (class "Default")
      (node (ref "U12") (pin "B13") (pinfunction "NC_B13") (pintype "unspecified"))
    )
    (net (code "209") (name "unconnected-(U12-NC-PadB14)") (class "Default")
      (node (ref "U12") (pin "B14") (pinfunction "NC_B14") (pintype "unspecified"))
    )
    (net (code "210") (name "unconnected-(U12-NC-PadC1)") (class "Default")
      (node (ref "U12") (pin "C1") (pinfunction "NC_C1") (pintype "unspecified"))
    )
    (net (code "211") (name "unconnected-(U12-NC-PadC3)") (class "Default")
      (node (ref "U12") (pin "C3") (pinfunction "NC_C3") (pintype "unspecified"))
    )
    (net (code "212") (name "unconnected-(U12-NC-PadC5)") (class "Default")
      (node (ref "U12") (pin "C5") (pinfunction "NC_C5") (pintype "unspecified"))
    )
    (net (code "213") (name "unconnected-(U12-NC-PadC7)") (class "Default")
      (node (ref "U12") (pin "C7") (pinfunction "NC_C7") (pintype "unspecified"))
    )
    (net (code "214") (name "unconnected-(U12-NC-PadC8)") (class "Default")
      (node (ref "U12") (pin "C8") (pinfunction "NC_C8") (pintype "unspecified"))
    )
    (net (code "215") (name "unconnected-(U12-NC-PadC9)") (class "Default")
      (node (ref "U12") (pin "C9") (pinfunction "NC_C9") (pintype "unspecified"))
    )
    (net (code "216") (name "unconnected-(U12-NC-PadC10)") (class "Default")
      (node (ref "U12") (pin "C10") (pinfunction "NC_C10") (pintype "unspecified"))
    )
    (net (code "217") (name "unconnected-(U12-NC-PadC11)") (class "Default")
      (node (ref "U12") (pin "C11") (pinfunction "NC_C11") (pintype "unspecified"))
    )
    (net (code "218") (name "unconnected-(U12-NC-PadC12)") (class "Default")
      (node (ref "U12") (pin "C12") (pinfunction "NC_C12") (pintype "unspecified"))
    )
    (net (code "219") (name "unconnected-(U12-NC-PadC13)") (class "Default")
      (node (ref "U12") (pin "C13") (pinfunction "NC_C13") (pintype "unspecified"))
    )
    (net (code "220") (name "unconnected-(U12-NC-PadC14)") (class "Default")
      (node (ref "U12") (pin "C14") (pinfunction "NC_C14") (pintype "unspecified"))
    )
    (net (code "221") (name "unconnected-(U12-NC-PadD1)") (class "Default")
      (node (ref "U12") (pin "D1") (pinfunction "NC_D1") (pintype "unspecified"))
    )
    (net (code "222") (name "unconnected-(U12-NC-PadD2)") (class "Default")
      (node (ref "U12") (pin "D2") (pinfunction "NC_D2") (pintype "unspecified"))
    )
    (net (code "223") (name "unconnected-(U12-NC-PadD3)") (class "Default")
      (node (ref "U12") (pin "D3") (pinfunction "NC_D3") (pintype "unspecified"))
    )
    (net (code "224") (name "unconnected-(U12-NC-PadD4)") (class "Default")
      (node (ref "U12") (pin "D4") (pinfunction "NC_D4") (pintype "unspecified"))
    )
    (net (code "225") (name "unconnected-(U12-NC-PadD12)") (class "Default")
      (node (ref "U12") (pin "D12") (pinfunction "NC_D12") (pintype "unspecified"))
    )
    (net (code "226") (name "unconnected-(U12-NC-PadD13)") (class "Default")
      (node (ref "U12") (pin "D13") (pinfunction "NC_D13") (pintype "unspecified"))
    )
    (net (code "227") (name "unconnected-(U12-NC-PadD14)") (class "Default")
      (node (ref "U12") (pin "D14") (pinfunction "NC_D14") (pintype "unspecified"))
    )
    (net (code "228") (name "unconnected-(U12-NC-PadE1)") (class "Default")
      (node (ref "U12") (pin "E1") (pinfunction "NC_E1") (pintype "unspecified"))
    )
    (net (code "229") (name "unconnected-(U12-NC-PadE2)") (class "Default")
      (node (ref "U12") (pin "E2") (pinfunction "NC_E2") (pintype "unspecified"))
    )
    (net (code "230") (name "unconnected-(U12-NC-PadE3)") (class "Default")
      (node (ref "U12") (pin "E3") (pinfunction "NC_E3") (pintype "unspecified"))
    )
    (net (code "231") (name "unconnected-(U12-NC-PadE12)") (class "Default")
      (node (ref "U12") (pin "E12") (pinfunction "NC_E12") (pintype "unspecified"))
    )
    (net (code "232") (name "unconnected-(U12-NC-PadE13)") (class "Default")
      (node (ref "U12") (pin "E13") (pinfunction "NC_E13") (pintype "unspecified"))
    )
    (net (code "233") (name "unconnected-(U12-NC-PadE14)") (class "Default")
      (node (ref "U12") (pin "E14") (pinfunction "NC_E14") (pintype "unspecified"))
    )
    (net (code "234") (name "unconnected-(U12-NC-PadF1)") (class "Default")
      (node (ref "U12") (pin "F1") (pinfunction "NC_F1") (pintype "unspecified"))
    )
    (net (code "235") (name "unconnected-(U12-NC-PadF2)") (class "Default")
      (node (ref "U12") (pin "F2") (pinfunction "NC_F2") (pintype "unspecified"))
    )
    (net (code "236") (name "unconnected-(U12-NC-PadF3)") (class "Default")
      (node (ref "U12") (pin "F3") (pinfunction "NC_F3") (pintype "unspecified"))
    )
    (net (code "237") (name "unconnected-(U12-NC-PadF12)") (class "Default")
      (node (ref "U12") (pin "F12") (pinfunction "NC_F12") (pintype "unspecified"))
    )
    (net (code "238") (name "unconnected-(U12-NC-PadF13)") (class "Default")
      (node (ref "U12") (pin "F13") (pinfunction "NC_F13") (pintype "unspecified"))
    )
    (net (code "239") (name "unconnected-(U12-NC-PadF14)") (class "Default")
      (node (ref "U12") (pin "F14") (pinfunction "NC_F14") (pintype "unspecified"))
    )
    (net (code "240") (name "unconnected-(U12-NC-PadG1)") (class "Default")
      (node (ref "U12") (pin "G1") (pinfunction "NC_G1") (pintype "unspecified"))
    )
    (net (code "241") (name "unconnected-(U12-NC-PadG2)") (class "Default")
      (node (ref "U12") (pin "G2") (pinfunction "NC_G2") (pintype "unspecified"))
    )
    (net (code "242") (name "unconnected-(U12-NC-PadG12)") (class "Default")
      (node (ref "U12") (pin "G12") (pinfunction "NC_G12") (pintype "unspecified"))
    )
    (net (code "243") (name "unconnected-(U12-NC-PadG13)") (class "Default")
      (node (ref "U12") (pin "G13") (pinfunction "NC_G13") (pintype "unspecified"))
    )
    (net (code "244") (name "unconnected-(U12-NC-PadG14)") (class "Default")
      (node (ref "U12") (pin "G14") (pinfunction "NC_G14") (pintype "unspecified"))
    )
    (net (code "245") (name "unconnected-(U12-NC-PadH1)") (class "Default")
      (node (ref "U12") (pin "H1") (pinfunction "NC_H1") (pintype "unspecified"))
    )
    (net (code "246") (name "unconnected-(U12-NC-PadH2)") (class "Default")
      (node (ref "U12") (pin "H2") (pinfunction "NC_H2") (pintype "unspecified"))
    )
    (net (code "247") (name "unconnected-(U12-NC-PadH3)") (class "Default")
      (node (ref "U12") (pin "H3") (pinfunction "NC_H3") (pintype "unspecified"))
    )
    (net (code "248") (name "unconnected-(U12-NC-PadH12)") (class "Default")
      (node (ref "U12") (pin "H12") (pinfunction "NC_H12") (pintype "unspecified"))
    )
    (net (code "249") (name "unconnected-(U12-NC-PadH13)") (class "Default")
      (node (ref "U12") (pin "H13") (pinfunction "NC_H13") (pintype "unspecified"))
    )
    (net (code "250") (name "unconnected-(U12-NC-PadH14)") (class "Default")
      (node (ref "U12") (pin "H14") (pinfunction "NC_H14") (pintype "unspecified"))
    )
    (net (code "251") (name "unconnected-(U12-NC-PadJ1)") (class "Default")
      (node (ref "U12") (pin "J1") (pinfunction "NC_J1") (pintype "unspecified"))
    )
    (net (code "252") (name "unconnected-(U12-NC-PadJ2)") (class "Default")
      (node (ref "U12") (pin "J2") (pinfunction "NC_J2") (pintype "unspecified"))
    )
    (net (code "253") (name "unconnected-(U12-NC-PadJ3)") (class "Default")
      (node (ref "U12") (pin "J3") (pinfunction "NC_J3") (pintype "unspecified"))
    )
    (net (code "254") (name "unconnected-(U12-NC-PadJ12)") (class "Default")
      (node (ref "U12") (pin "J12") (pinfunction "NC_J12") (pintype "unspecified"))
    )
    (net (code "255") (name "unconnected-(U12-NC-PadJ13)") (class "Default")
      (node (ref "U12") (pin "J13") (pinfunction "NC_J13") (pintype "unspecified"))
    )
    (net (code "256") (name "unconnected-(U12-NC-PadJ14)") (class "Default")
      (node (ref "U12") (pin "J14") (pinfunction "NC_J14") (pintype "unspecified"))
    )
    (net (code "257") (name "unconnected-(U12-NC-PadK1)") (class "Default")
      (node (ref "U12") (pin "K1") (pinfunction "NC_K1") (pintype "unspecified"))
    )
    (net (code "258") (name "unconnected-(U12-NC-PadK2)") (class "Default")
      (node (ref "U12") (pin "K2") (pinfunction "NC_K2") (pintype "unspecified"))
    )
    (net (code "259") (name "unconnected-(U12-NC-PadK3)") (class "Default")
      (node (ref "U12") (pin "K3") (pinfunction "NC_K3") (pintype "unspecified"))
    )
    (net (code "260") (name "unconnected-(U12-NC-PadK12)") (class "Default")
      (node (ref "U12") (pin "K12") (pinfunction "NC_K12") (pintype "unspecified"))
    )
    (net (code "261") (name "unconnected-(U12-NC-PadK13)") (class "Default")
      (node (ref "U12") (pin "K13") (pinfunction "NC_K13") (pintype "unspecified"))
    )
    (net (code "262") (name "unconnected-(U12-NC-PadK14)") (class "Default")
      (node (ref "U12") (pin "K14") (pinfunction "NC_K14") (pintype "unspecified"))
    )
    (net (code "263") (name "unconnected-(U12-NC-PadL1)") (class "Default")
      (node (ref "U12") (pin "L1") (pinfunction "NC_L1") (pintype "unspecified"))
    )
    (net (code "264") (name "unconnected-(U12-NC-PadL2)") (class "Default")
      (node (ref "U12") (pin "L2") (pinfunction "NC_L2") (pintype "unspecified"))
    )
    (net (code "265") (name "unconnected-(U12-NC-PadL3)") (class "Default")
      (node (ref "U12") (pin "L3") (pinfunction "NC_L3") (pintype "unspecified"))
    )
    (net (code "266") (name "unconnected-(U12-NC-PadL12)") (class "Default")
      (node (ref "U12") (pin "L12") (pinfunction "NC_L12") (pintype "unspecified"))
    )
    (net (code "267") (name "unconnected-(U12-NC-PadL13)") (class "Default")
      (node (ref "U12") (pin "L13") (pinfunction "NC_L13") (pintype "unspecified"))
    )
    (net (code "268") (name "unconnected-(U12-NC-PadL14)") (class "Default")
      (node (ref "U12") (pin "L14") (pinfunction "NC_L14") (pintype "unspecified"))
    )
    (net (code "269") (name "unconnected-(U12-NC-PadM1)") (class "Default")
      (node (ref "U12") (pin "M1") (pinfunction "NC_M1") (pintype "unspecified"))
    )
    (net (code "270") (name "unconnected-(U12-NC-PadM2)") (class "Default")
      (node (ref "U12") (pin "M2") (pinfunction "NC_M2") (pintype "unspecified"))
    )
    (net (code "271") (name "unconnected-(U12-NC-PadM3)") (class "Default")
      (node (ref "U12") (pin "M3") (pinfunction "NC_M3") (pintype "unspecified"))
    )
    (net (code "272") (name "unconnected-(U12-NC-PadM7)") (class "Default")
      (node (ref "U12") (pin "M7") (pinfunction "NC_M7") (pintype "unspecified"))
    )
    (net (code "273") (name "unconnected-(U12-NC-PadM8)") (class "Default")
      (node (ref "U12") (pin "M8") (pinfunction "NC_M8") (pintype "unspecified"))
    )
    (net (code "274") (name "unconnected-(U12-NC-PadM9)") (class "Default")
      (node (ref "U12") (pin "M9") (pinfunction "NC_M9") (pintype "unspecified"))
    )
    (net (code "275") (name "unconnected-(U12-NC-PadM10)") (class "Default")
      (node (ref "U12") (pin "M10") (pinfunction "NC_M10") (pintype "unspecified"))
    )
    (net (code "276") (name "unconnected-(U12-NC-PadM11)") (class "Default")
      (node (ref "U12") (pin "M11") (pinfunction "NC_M11") (pintype "unspecified"))
    )
    (net (code "277") (name "unconnected-(U12-NC-PadM12)") (class "Default")
      (node (ref "U12") (pin "M12") (pinfunction "NC_M12") (pintype "unspecified"))
    )
    (net (code "278") (name "unconnected-(U12-NC-PadM13)") (class "Default")
      (node (ref "U12") (pin "M13") (pinfunction "NC_M13") (pintype "unspecified"))
    )
    (net (code "279") (name "unconnected-(U12-NC-PadM14)") (class "Default")
      (node (ref "U12") (pin "M14") (pinfunction "NC_M14") (pintype "unspecified"))
    )
    (net (code "280") (name "unconnected-(U12-NC-PadN1)") (class "Default")
      (node (ref "U12") (pin "N1") (pinfunction "NC_N1") (pintype "unspecified"))
    )
    (net (code "281") (name "unconnected-(U12-NC-PadN3)") (class "Default")
      (node (ref "U12") (pin "N3") (pinfunction "NC_N3") (pintype "unspecified"))
    )
    (net (code "282") (name "unconnected-(U12-NC-PadN6)") (class "Default")
      (node (ref "U12") (pin "N6") (pinfunction "NC_N6") (pintype "unspecified"))
    )
    (net (code "283") (name "unconnected-(U12-NC-PadN7)") (class "Default")
      (node (ref "U12") (pin "N7") (pinfunction "NC_N7") (pintype "unspecified"))
    )
    (net (code "284") (name "unconnected-(U12-NC-PadN8)") (class "Default")
      (node (ref "U12") (pin "N8") (pinfunction "NC_N8") (pintype "unspecified"))
    )
    (net (code "285") (name "unconnected-(U12-NC-PadN9)") (class "Default")
      (node (ref "U12") (pin "N9") (pinfunction "NC_N9") (pintype "unspecified"))
    )
    (net (code "286") (name "unconnected-(U12-NC-PadN10)") (class "Default")
      (node (ref "U12") (pin "N10") (pinfunction "NC_N10") (pintype "unspecified"))
    )
    (net (code "287") (name "unconnected-(U12-NC-PadN11)") (class "Default")
      (node (ref "U12") (pin "N11") (pinfunction "NC_N11") (pintype "unspecified"))
    )
    (net (code "288") (name "unconnected-(U12-NC-PadN12)") (class "Default")
      (node (ref "U12") (pin "N12") (pinfunction "NC_N12") (pintype "unspecified"))
    )
    (net (code "289") (name "unconnected-(U12-NC-PadN13)") (class "Default")
      (node (ref "U12") (pin "N13") (pinfunction "NC_N13") (pintype "unspecified"))
    )
    (net (code "290") (name "unconnected-(U12-NC-PadN14)") (class "Default")
      (node (ref "U12") (pin "N14") (pinfunction "NC_N14") (pintype "unspecified"))
    )
    (net (code "291") (name "unconnected-(U12-NC-PadP1)") (class "Default")
      (node (ref "U12") (pin "P1") (pinfunction "NC_P1") (pintype "unspecified"))
    )
    (net (code "292") (name "unconnected-(U12-NC-PadP2)") (class "Default")
      (node (ref "U12") (pin "P2") (pinfunction "NC_P2") (pintype "unspecified"))
    )
    (net (code "293") (name "unconnected-(U12-NC-PadP7)") (class "Default")
      (node (ref "U12") (pin "P7") (pinfunction "NC_P7") (pintype "unspecified"))
    )
    (net (code "294") (name "unconnected-(U12-NC-PadP8)") (class "Default")
      (node (ref "U12") (pin "P8") (pinfunction "NC_P8") (pintype "unspecified"))
    )
    (net (code "295") (name "unconnected-(U12-NC-PadP9)") (class "Default")
      (node (ref "U12") (pin "P9") (pinfunction "NC_P9") (pintype "unspecified"))
    )
    (net (code "296") (name "unconnected-(U12-NC-PadP11)") (class "Default")
      (node (ref "U12") (pin "P11") (pinfunction "NC_P11") (pintype "unspecified"))
    )
    (net (code "297") (name "unconnected-(U12-NC-PadP12)") (class "Default")
      (node (ref "U12") (pin "P12") (pinfunction "NC_P12") (pintype "unspecified"))
    )
    (net (code "298") (name "unconnected-(U12-NC-PadP13)") (class "Default")
      (node (ref "U12") (pin "P13") (pinfunction "NC_P13") (pintype "unspecified"))
    )
    (net (code "299") (name "unconnected-(U12-NC-PadP14)") (class "Default")
      (node (ref "U12") (pin "P14") (pinfunction "NC_P14") (pintype "unspecified"))
    )
    (net (code "300") (name "unconnected-(U12-RFU-PadA7)") (class "Default")
      (node (ref "U12") (pin "A7") (pinfunction "RFU_A7") (pintype "unspecified"))
    )
    (net (code "301") (name "unconnected-(U12-RFU-PadE5)") (class "Default")
      (node (ref "U12") (pin "E5") (pinfunction "RFU_E5") (pintype "unspecified"))
    )
    (net (code "302") (name "unconnected-(U12-RFU-PadE8)") (class "Default")
      (node (ref "U12") (pin "E8") (pinfunction "RFU_E8") (pintype "unspecified"))
    )
    (net (code "303") (name "unconnected-(U12-RFU-PadE9)") (class "Default")
      (node (ref "U12") (pin "E9") (pinfunction "RFU_E9") (pintype "unspecified"))
    )
    (net (code "304") (name "unconnected-(U12-RFU-PadE10)") (class "Default")
      (node (ref "U12") (pin "E10") (pinfunction "RFU_E10") (pintype "unspecified"))
    )
    (net (code "305") (name "unconnected-(U12-RFU-PadF10)") (class "Default")
      (node (ref "U12") (pin "F10") (pinfunction "RFU_F10") (pintype "unspecified"))
    )
    (net (code "306") (name "unconnected-(U12-RFU-PadG3)") (class "Default")
      (node (ref "U12") (pin "G3") (pinfunction "RFU_G3") (pintype "unspecified"))
    )
    (net (code "307") (name "unconnected-(U12-RFU-PadG10)") (class "Default")
      (node (ref "U12") (pin "G10") (pinfunction "RFU_G10") (pintype "unspecified"))
    )
    (net (code "308") (name "unconnected-(U12-RFU-PadK6)") (class "Default")
      (node (ref "U12") (pin "K6") (pinfunction "RFU_K6") (pintype "unspecified"))
    )
    (net (code "309") (name "unconnected-(U12-RFU-PadK7)") (class "Default")
      (node (ref "U12") (pin "K7") (pinfunction "RFU_K7") (pintype "unspecified"))
    )
    (net (code "310") (name "unconnected-(U12-RFU-PadK10)") (class "Default")
      (node (ref "U12") (pin "K10") (pinfunction "RFU_K10") (pintype "unspecified"))
    )
    (net (code "311") (name "unconnected-(U12-RFU-PadP10)") (class "Default")
      (node (ref "U12") (pin "P10") (pinfunction "RFU_P10") (pintype "unspecified"))
    )
    (net (code "312") (name "unconnected-(U12-RSTN-PadK5)") (class "Default")
      (node (ref "U12") (pin "K5") (pinfunction "RSTN_K5") (pintype "unspecified"))
    )
    (net (code "313") (name "unconnected-(U12-VCC-PadE6)") (class "Default")
      (node (ref "U12") (pin "E6") (pinfunction "VCC_E6") (pintype "unspecified"))
    )
    (net (code "314") (name "unconnected-(U12-VCC-PadF5)") (class "Default")
      (node (ref "U12") (pin "F5") (pinfunction "VCC_F5") (pintype "unspecified"))
    )
    (net (code "315") (name "unconnected-(U12-VCC-PadJ10)") (class "Default")
      (node (ref "U12") (pin "J10") (pinfunction "VCC_J10") (pintype "unspecified"))
    )
    (net (code "316") (name "unconnected-(U12-VCC-PadK9)") (class "Default")
      (node (ref "U12") (pin "K9") (pinfunction "VCC_K9") (pintype "unspecified"))
    )
    (net (code "317") (name "unconnected-(U12-VCCQ-PadC6)") (class "Default")
      (node (ref "U12") (pin "C6") (pinfunction "VCCQ_C6") (pintype "unspecified"))
    )
    (net (code "318") (name "unconnected-(U12-VCCQ-PadM4)") (class "Default")
      (node (ref "U12") (pin "M4") (pinfunction "VCCQ_M4") (pintype "unspecified"))
    )
    (net (code "319") (name "unconnected-(U12-VCCQ-PadN4)") (class "Default")
      (node (ref "U12") (pin "N4") (pinfunction "VCCQ_N4") (pintype "unspecified"))
    )
    (net (code "320") (name "unconnected-(U12-VCCQ-PadP3)") (class "Default")
      (node (ref "U12") (pin "P3") (pinfunction "VCCQ_P3") (pintype "unspecified"))
    )
    (net (code "321") (name "unconnected-(U12-VCCQ-PadP5)") (class "Default")
      (node (ref "U12") (pin "P5") (pinfunction "VCCQ_P5") (pintype "unspecified"))
    )
    (net (code "322") (name "unconnected-(U12-VDDI-PadC2)") (class "Default")
      (node (ref "U12") (pin "C2") (pinfunction "VDDI_C2") (pintype "unspecified"))
    )
    (net (code "323") (name "unconnected-(U12-VSS-PadA6)") (class "Default")
      (node (ref "U12") (pin "A6") (pinfunction "VSS_A6") (pintype "unspecified"))
    )
    (net (code "324") (name "unconnected-(U12-VSS-PadC4)") (class "Default")
      (node (ref "U12") (pin "C4") (pinfunction "VSS_C4") (pintype "unspecified"))
    )
    (net (code "325") (name "unconnected-(U12-VSS-PadE7)") (class "Default")
      (node (ref "U12") (pin "E7") (pinfunction "VSS_E7") (pintype "unspecified"))
    )
    (net (code "326") (name "unconnected-(U12-VSS-PadG5)") (class "Default")
      (node (ref "U12") (pin "G5") (pinfunction "VSS_G5") (pintype "unspecified"))
    )
    (net (code "327") (name "unconnected-(U12-VSS-PadH10)") (class "Default")
      (node (ref "U12") (pin "H10") (pinfunction "VSS_H10") (pintype "unspecified"))
    )
    (net (code "328") (name "unconnected-(U12-VSS-PadJ5)") (class "Default")
      (node (ref "U12") (pin "J5") (pinfunction "VSS_J5") (pintype "unspecified"))
    )
    (net (code "329") (name "unconnected-(U12-VSS-PadK8)") (class "Default")
      (node (ref "U12") (pin "K8") (pinfunction "VSS_K8") (pintype "unspecified"))
    )
    (net (code "330") (name "unconnected-(U12-VSS-PadN2)") (class "Default")
      (node (ref "U12") (pin "N2") (pinfunction "VSS_N2") (pintype "unspecified"))
    )
    (net (code "331") (name "unconnected-(U12-VSS-PadN5)") (class "Default")
      (node (ref "U12") (pin "N5") (pinfunction "VSS_N5") (pintype "unspecified"))
    )
    (net (code "332") (name "unconnected-(U12-VSS-PadP4)") (class "Default")
      (node (ref "U12") (pin "P4") (pinfunction "VSS_P4") (pintype "unspecified"))
    )
    (net (code "333") (name "unconnected-(U12-VSS-PadP6)") (class "Default")
      (node (ref "U12") (pin "P6") (pinfunction "VSS_P6") (pintype "unspecified"))
    )
    (net (code "334") (name "usb_D+") (class "Default")
      (node (ref "U1") (pin "41") (pinfunction "20_41") (pintype "bidirectional"))
      (node (ref "U9") (pin "2") (pinfunction "2_2") (pintype "unspecified"))
    )
    (net (code "335") (name "usb_D-") (class "Default")
      (node (ref "U1") (pin "42") (pinfunction "19_42") (pintype "bidirectional"))
      (node (ref "U9") (pin "1") (pinfunction "1_1") (pintype "unspecified"))
    )
  )
)
